# MCU3.net
KiCad netlist of a schematic drawn in Altium Designer
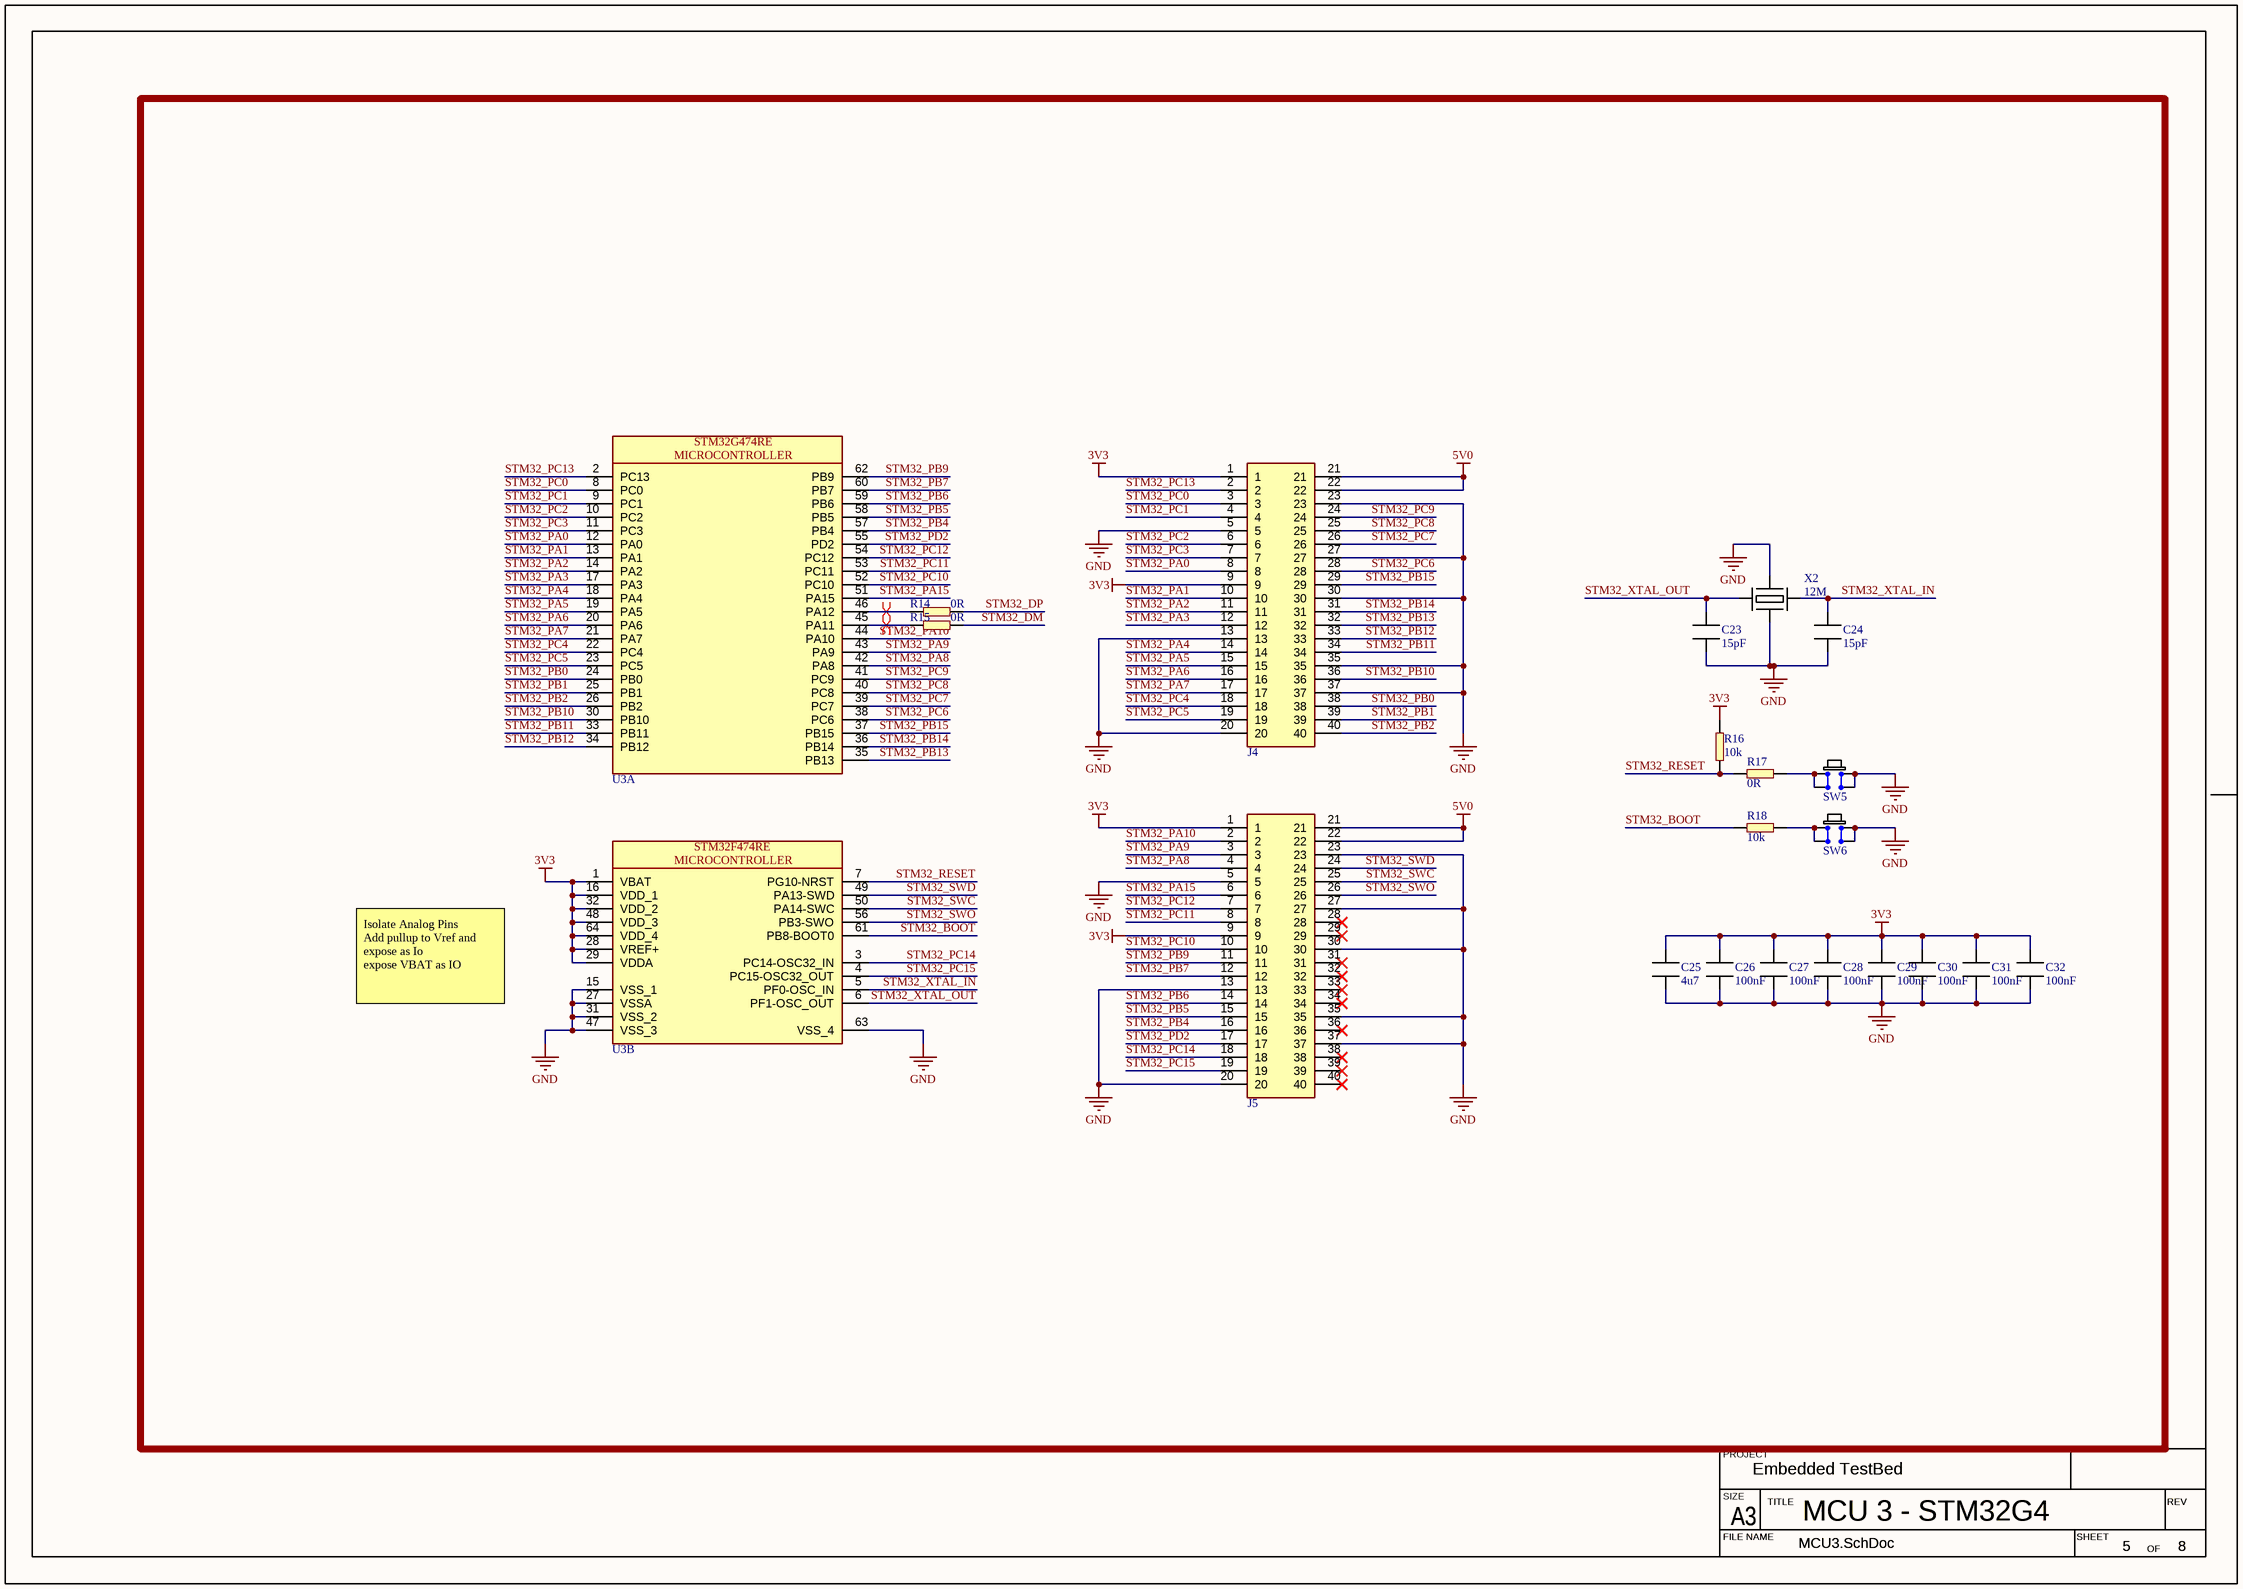
[diagram p0: MCU3.SchDoc]

(export (version "E")
  (design (tool "Eeschema 10.0.6"))
  (components
    (comp (ref "C23")
      (value "15pF")
      (footprint "CAPC2012X13L")
      (description "Chip Capacitor, 2-Leads, Body 2.00x1.25mm, IPC High Density")
      (fields (field (name "Comment") "MLCC_0805"))
      (libsource (lib "Capacitor") (part "MLCC_0805"))
    )
    (comp (ref "C24")
      (value "15pF")
      (footprint "CAPC2012X13L")
      (description "Chip Capacitor, 2-Leads, Body 2.00x1.25mm, IPC High Density")
      (fields (field (name "Comment") "MLCC_0805"))
      (libsource (lib "Capacitor") (part "MLCC_0805"))
    )
    (comp (ref "C25")
      (value "4u7")
      (footprint "CAPC2012X13L")
      (description "Chip Capacitor, 2-Leads, Body 2.00x1.25mm, IPC High Density")
      (fields (field (name "Comment") "MLCC_0805"))
      (libsource (lib "Capacitor") (part "MLCC_0805"))
    )
    (comp (ref "C26")
      (value "100nF")
      (footprint "CAPC2012X13L")
      (description "Chip Capacitor, 2-Leads, Body 2.00x1.25mm, IPC High Density")
      (fields (field (name "Comment") "MLCC_0805"))
      (libsource (lib "Capacitor") (part "MLCC_0805"))
    )
    (comp (ref "C27")
      (value "100nF")
      (footprint "CAPC2012X13L")
      (description "Chip Capacitor, 2-Leads, Body 2.00x1.25mm, IPC High Density")
      (fields (field (name "Comment") "MLCC_0805"))
      (libsource (lib "Capacitor") (part "MLCC_0805"))
    )
    (comp (ref "C28")
      (value "100nF")
      (footprint "CAPC2012X13L")
      (description "Chip Capacitor, 2-Leads, Body 2.00x1.25mm, IPC High Density")
      (fields (field (name "Comment") "MLCC_0805"))
      (libsource (lib "Capacitor") (part "MLCC_0805"))
    )
    (comp (ref "C29")
      (value "100nF")
      (footprint "CAPC2012X13L")
      (description "Chip Capacitor, 2-Leads, Body 2.00x1.25mm, IPC High Density")
      (fields (field (name "Comment") "MLCC_0805"))
      (libsource (lib "Capacitor") (part "MLCC_0805"))
    )
    (comp (ref "C30")
      (value "100nF")
      (footprint "CAPC2012X13L")
      (description "Chip Capacitor, 2-Leads, Body 2.00x1.25mm, IPC High Density")
      (fields (field (name "Comment") "MLCC_0805"))
      (libsource (lib "Capacitor") (part "MLCC_0805"))
    )
    (comp (ref "C31")
      (value "100nF")
      (footprint "CAPC2012X13L")
      (description "Chip Capacitor, 2-Leads, Body 2.00x1.25mm, IPC High Density")
      (fields (field (name "Comment") "MLCC_0805"))
      (libsource (lib "Capacitor") (part "MLCC_0805"))
    )
    (comp (ref "C32")
      (value "100nF")
      (footprint "CAPC2012X13L")
      (description "Chip Capacitor, 2-Leads, Body 2.00x1.25mm, IPC High Density")
      (fields (field (name "Comment") "MLCC_0805"))
      (libsource (lib "Capacitor") (part "MLCC_0805"))
    )
    (comp (ref "J4")
      (value "40PX2R_M_1")
      (footprint "40PX2R_Male_THT")
      (description "Berg Connector Header Through Hole  40 Position 0.100\" (2.54mm)")
      (libsource (lib "PinHeader") (part "40PX2R_M_1"))
    )
    (comp (ref "J5")
      (value "40PX2R_M_1")
      (footprint "40PX2R_Male_THT")
      (description "Berg Connector Header Through Hole  40 Position 0.100\" (2.54mm)")
      (libsource (lib "PinHeader") (part "40PX2R_M_1"))
    )
    (comp (ref "R14")
      (value "0R")
      (footprint "RES_0805")
      (description "RES_0805")
      (fields (field (name "Comment") "ERP_101-1"))
      (libsource (lib "Resistor") (part "RES_0805"))
    )
    (comp (ref "R15")
      (value "0R")
      (footprint "RES_0805")
      (description "RES_0805")
      (fields (field (name "Comment") "ERP_101-1"))
      (libsource (lib "Resistor") (part "RES_0805"))
    )
    (comp (ref "R16")
      (value "10k")
      (footprint "RES_0805")
      (description "RES_0805")
      (fields (field (name "Comment") "ERP_101-1"))
      (libsource (lib "") (part "RES_0805_1"))
    )
    (comp (ref "R17")
      (value "0R")
      (footprint "RES_0805")
      (description "RES_0805")
      (fields (field (name "Comment") "ERP_101-1"))
      (libsource (lib "Resistor") (part "RES_0805"))
    )
    (comp (ref "R18")
      (value "10k")
      (footprint "RES_0805")
      (description "RES_0805")
      (fields (field (name "Comment") "ERP_101-1"))
      (libsource (lib "Resistor") (part "RES_0805"))
    )
    (comp (ref "SW5")
      (value "Generic6X6")
      (footprint "Generic6X6")
      (description "Tactile Switch SPST-NO Top Actuated Surface Mount")
      (libsource (lib "Switch") (part "Generic6X6"))
    )
    (comp (ref "SW6")
      (value "Generic6X6")
      (footprint "Generic6X6")
      (description "Tactile Switch SPST-NO Top Actuated Surface Mount")
      (libsource (lib "Switch") (part "Generic6X6"))
    )
    (comp (ref "U3")
      (value "STM32G474RE")
      (footprint "TSQFP50P1200X1200X160-64L")
      (description "512KB 1.71V~3.6V ARM-M4 128KB 170MHz FLASH 52 LQFP-64(10x10) Microcontrollers (MCU/MPU/SOC) ROHS")
      (libsource (lib "MCU") (part "STM32G474RE"))
    )
    (comp (ref "X2")
      (value "12M")
      (footprint "ABM8")
      (description "CRYS_L3.2_W2.5")
      (fields (field (name "Comment") "ABM8"))
      (libsource (lib "Crystal") (part "ABM8"))
    )
  )
  (nets
    (net (code "1") (name "/STM32_BOOT") (class "Default")
      (node (ref "R18") (pin "2") (pinfunction "2_2") (pintype "passive"))
      (node (ref "U3") (pin "61") (pinfunction "PB8-BOOT0_61") (pintype "passive"))
    )
    (net (code "2") (name "/STM32_DM") (class "Default")
      (node (ref "R15") (pin "1") (pinfunction "1_1") (pintype "passive"))
    )
    (net (code "3") (name "/STM32_DP") (class "Default")
      (node (ref "R14") (pin "1") (pinfunction "1_1") (pintype "passive"))
    )
    (net (code "4") (name "/STM32_PA0") (class "Default")
      (node (ref "J4") (pin "8") (pinfunction "8_8") (pintype "passive"))
      (node (ref "U3") (pin "12") (pinfunction "PA0_12") (pintype "passive"))
    )
    (net (code "5") (name "/STM32_PA1") (class "Default")
      (node (ref "J4") (pin "10") (pinfunction "10_10") (pintype "passive"))
      (node (ref "U3") (pin "13") (pinfunction "PA1_13") (pintype "passive"))
    )
    (net (code "6") (name "/STM32_PA2") (class "Default")
      (node (ref "J4") (pin "11") (pinfunction "11_11") (pintype "passive"))
      (node (ref "U3") (pin "14") (pinfunction "PA2_14") (pintype "passive"))
    )
    (net (code "7") (name "/STM32_PA3") (class "Default")
      (node (ref "J4") (pin "12") (pinfunction "12_12") (pintype "passive"))
      (node (ref "U3") (pin "17") (pinfunction "PA3_17") (pintype "passive"))
    )
    (net (code "8") (name "/STM32_PA4") (class "Default")
      (node (ref "J4") (pin "14") (pinfunction "14_14") (pintype "passive"))
      (node (ref "U3") (pin "18") (pinfunction "PA4_18") (pintype "passive"))
    )
    (net (code "9") (name "/STM32_PA5") (class "Default")
      (node (ref "J4") (pin "15") (pinfunction "15_15") (pintype "passive"))
      (node (ref "U3") (pin "19") (pinfunction "PA5_19") (pintype "passive"))
    )
    (net (code "10") (name "/STM32_PA6") (class "Default")
      (node (ref "J4") (pin "16") (pinfunction "16_16") (pintype "passive"))
      (node (ref "U3") (pin "20") (pinfunction "PA6_20") (pintype "passive"))
    )
    (net (code "11") (name "/STM32_PA7") (class "Default")
      (node (ref "J4") (pin "17") (pinfunction "17_17") (pintype "passive"))
      (node (ref "U3") (pin "21") (pinfunction "PA7_21") (pintype "passive"))
    )
    (net (code "12") (name "/STM32_PA8") (class "Default")
      (node (ref "J5") (pin "4") (pinfunction "4_4") (pintype "passive"))
      (node (ref "U3") (pin "42") (pinfunction "PA8_42") (pintype "passive"))
    )
    (net (code "13") (name "/STM32_PA9") (class "Default")
      (node (ref "J5") (pin "3") (pinfunction "3_3") (pintype "passive"))
      (node (ref "U3") (pin "43") (pinfunction "PA9_43") (pintype "passive"))
    )
    (net (code "14") (name "/STM32_PA10") (class "Default")
      (node (ref "J5") (pin "2") (pinfunction "2_2") (pintype "passive"))
      (node (ref "U3") (pin "44") (pinfunction "PA10_44") (pintype "passive"))
    )
    (net (code "15") (name "/STM32_PA15") (class "Default")
      (node (ref "J5") (pin "6") (pinfunction "6_6") (pintype "passive"))
      (node (ref "U3") (pin "51") (pinfunction "PA15_51") (pintype "passive"))
    )
    (net (code "16") (name "/STM32_PB0") (class "Default")
      (node (ref "J4") (pin "38") (pinfunction "38_38") (pintype "passive"))
      (node (ref "U3") (pin "24") (pinfunction "PB0_24") (pintype "passive"))
    )
    (net (code "17") (name "/STM32_PB1") (class "Default")
      (node (ref "J4") (pin "39") (pinfunction "39_39") (pintype "passive"))
      (node (ref "U3") (pin "25") (pinfunction "PB1_25") (pintype "passive"))
    )
    (net (code "18") (name "/STM32_PB2") (class "Default")
      (node (ref "J4") (pin "40") (pinfunction "40_40") (pintype "passive"))
      (node (ref "U3") (pin "26") (pinfunction "PB2_26") (pintype "passive"))
    )
    (net (code "19") (name "/STM32_PB4") (class "Default")
      (node (ref "J5") (pin "16") (pinfunction "16_16") (pintype "passive"))
      (node (ref "U3") (pin "57") (pinfunction "PB4_57") (pintype "passive"))
    )
    (net (code "20") (name "/STM32_PB5") (class "Default")
      (node (ref "J5") (pin "15") (pinfunction "15_15") (pintype "passive"))
      (node (ref "U3") (pin "58") (pinfunction "PB5_58") (pintype "passive"))
    )
    (net (code "21") (name "/STM32_PB6") (class "Default")
      (node (ref "J5") (pin "14") (pinfunction "14_14") (pintype "passive"))
      (node (ref "U3") (pin "59") (pinfunction "PB6_59") (pintype "passive"))
    )
    (net (code "22") (name "/STM32_PB7") (class "Default")
      (node (ref "J5") (pin "12") (pinfunction "12_12") (pintype "passive"))
      (node (ref "U3") (pin "60") (pinfunction "PB7_60") (pintype "passive"))
    )
    (net (code "23") (name "/STM32_PB9") (class "Default")
      (node (ref "J5") (pin "11") (pinfunction "11_11") (pintype "passive"))
      (node (ref "U3") (pin "62") (pinfunction "PB9_62") (pintype "passive"))
    )
    (net (code "24") (name "/STM32_PB10") (class "Default")
      (node (ref "J4") (pin "36") (pinfunction "36_36") (pintype "passive"))
      (node (ref "U3") (pin "30") (pinfunction "PB10_30") (pintype "passive"))
    )
    (net (code "25") (name "/STM32_PB11") (class "Default")
      (node (ref "J4") (pin "34") (pinfunction "34_34") (pintype "passive"))
      (node (ref "U3") (pin "33") (pinfunction "PB11_33") (pintype "passive"))
    )
    (net (code "26") (name "/STM32_PB12") (class "Default")
      (node (ref "J4") (pin "33") (pinfunction "33_33") (pintype "passive"))
      (node (ref "U3") (pin "34") (pinfunction "PB12_34") (pintype "passive"))
    )
    (net (code "27") (name "/STM32_PB13") (class "Default")
      (node (ref "J4") (pin "32") (pinfunction "32_32") (pintype "passive"))
      (node (ref "U3") (pin "35") (pinfunction "PB13_35") (pintype "passive"))
    )
    (net (code "28") (name "/STM32_PB14") (class "Default")
      (node (ref "J4") (pin "31") (pinfunction "31_31") (pintype "passive"))
      (node (ref "U3") (pin "36") (pinfunction "PB14_36") (pintype "passive"))
    )
    (net (code "29") (name "/STM32_PB15") (class "Default")
      (node (ref "J4") (pin "29") (pinfunction "29_29") (pintype "passive"))
      (node (ref "U3") (pin "37") (pinfunction "PB15_37") (pintype "passive"))
    )
    (net (code "30") (name "/STM32_PC0") (class "Default")
      (node (ref "J4") (pin "3") (pinfunction "3_3") (pintype "passive"))
      (node (ref "U3") (pin "8") (pinfunction "PC0_8") (pintype "passive"))
    )
    (net (code "31") (name "/STM32_PC1") (class "Default")
      (node (ref "J4") (pin "4") (pinfunction "4_4") (pintype "passive"))
      (node (ref "U3") (pin "9") (pinfunction "PC1_9") (pintype "passive"))
    )
    (net (code "32") (name "/STM32_PC2") (class "Default")
      (node (ref "J4") (pin "6") (pinfunction "6_6") (pintype "passive"))
      (node (ref "U3") (pin "10") (pinfunction "PC2_10") (pintype "passive"))
    )
    (net (code "33") (name "/STM32_PC3") (class "Default")
      (node (ref "J4") (pin "7") (pinfunction "7_7") (pintype "passive"))
      (node (ref "U3") (pin "11") (pinfunction "PC3_11") (pintype "passive"))
    )
    (net (code "34") (name "/STM32_PC4") (class "Default")
      (node (ref "J4") (pin "18") (pinfunction "18_18") (pintype "passive"))
      (node (ref "U3") (pin "22") (pinfunction "PC4_22") (pintype "passive"))
    )
    (net (code "35") (name "/STM32_PC5") (class "Default")
      (node (ref "J4") (pin "19") (pinfunction "19_19") (pintype "passive"))
      (node (ref "U3") (pin "23") (pinfunction "PC5_23") (pintype "passive"))
    )
    (net (code "36") (name "/STM32_PC6") (class "Default")
      (node (ref "J4") (pin "28") (pinfunction "28_28") (pintype "passive"))
      (node (ref "U3") (pin "38") (pinfunction "PC6_38") (pintype "passive"))
    )
    (net (code "37") (name "/STM32_PC7") (class "Default")
      (node (ref "J4") (pin "26") (pinfunction "26_26") (pintype "passive"))
      (node (ref "U3") (pin "39") (pinfunction "PC7_39") (pintype "passive"))
    )
    (net (code "38") (name "/STM32_PC8") (class "Default")
      (node (ref "J4") (pin "25") (pinfunction "25_25") (pintype "passive"))
      (node (ref "U3") (pin "40") (pinfunction "PC8_40") (pintype "passive"))
    )
    (net (code "39") (name "/STM32_PC9") (class "Default")
      (node (ref "J4") (pin "24") (pinfunction "24_24") (pintype "passive"))
      (node (ref "U3") (pin "41") (pinfunction "PC9_41") (pintype "passive"))
    )
    (net (code "40") (name "/STM32_PC10") (class "Default")
      (node (ref "J5") (pin "10") (pinfunction "10_10") (pintype "passive"))
      (node (ref "U3") (pin "52") (pinfunction "PC10_52") (pintype "passive"))
    )
    (net (code "41") (name "/STM32_PC11") (class "Default")
      (node (ref "J5") (pin "8") (pinfunction "8_8") (pintype "passive"))
      (node (ref "U3") (pin "53") (pinfunction "PC11_53") (pintype "passive"))
    )
    (net (code "42") (name "/STM32_PC12") (class "Default")
      (node (ref "J5") (pin "7") (pinfunction "7_7") (pintype "passive"))
      (node (ref "U3") (pin "54") (pinfunction "PC12_54") (pintype "passive"))
    )
    (net (code "43") (name "/STM32_PC13") (class "Default")
      (node (ref "J4") (pin "2") (pinfunction "2_2") (pintype "passive"))
      (node (ref "U3") (pin "2") (pinfunction "PC13_2") (pintype "passive"))
    )
    (net (code "44") (name "/STM32_PC14") (class "Default")
      (node (ref "J5") (pin "18") (pinfunction "18_18") (pintype "passive"))
      (node (ref "U3") (pin "3") (pinfunction "PC14-OSC32_IN_3") (pintype "passive"))
    )
    (net (code "45") (name "/STM32_PC15") (class "Default")
      (node (ref "J5") (pin "19") (pinfunction "19_19") (pintype "passive"))
      (node (ref "U3") (pin "4") (pinfunction "PC15-OSC32_OUT_4") (pintype "passive"))
    )
    (net (code "46") (name "/STM32_PD2") (class "Default")
      (node (ref "J5") (pin "17") (pinfunction "17_17") (pintype "passive"))
      (node (ref "U3") (pin "55") (pinfunction "PD2_55") (pintype "passive"))
    )
    (net (code "47") (name "/STM32_RESET") (class "Default")
      (node (ref "R16") (pin "2") (pinfunction "2_2") (pintype "passive"))
      (node (ref "R17") (pin "2") (pinfunction "2_2") (pintype "passive"))
      (node (ref "U3") (pin "7") (pinfunction "PG10-NRST_7") (pintype "passive"))
    )
    (net (code "48") (name "/STM32_SWC") (class "Default")
      (node (ref "J5") (pin "25") (pinfunction "25_25") (pintype "passive"))
      (node (ref "U3") (pin "50") (pinfunction "PA14-SWC_50") (pintype "passive"))
    )
    (net (code "49") (name "/STM32_SWD") (class "Default")
      (node (ref "J5") (pin "24") (pinfunction "24_24") (pintype "passive"))
      (node (ref "U3") (pin "49") (pinfunction "PA13-SWD_49") (pintype "passive"))
    )
    (net (code "50") (name "/STM32_SWO") (class "Default")
      (node (ref "J5") (pin "26") (pinfunction "26_26") (pintype "passive"))
      (node (ref "U3") (pin "56") (pinfunction "PB3-SWO_56") (pintype "passive"))
    )
    (net (code "51") (name "/STM32_XTAL_IN") (class "Default")
      (node (ref "C24") (pin "1") (pinfunction "1_1") (pintype "passive"))
      (node (ref "U3") (pin "5") (pinfunction "PF0-OSC_IN_5") (pintype "passive"))
      (node (ref "X2") (pin "3") (pinfunction "3_3") (pintype "passive"))
    )
    (net (code "52") (name "/STM32_XTAL_OUT") (class "Default")
      (node (ref "C23") (pin "1") (pinfunction "1_1") (pintype "passive"))
      (node (ref "U3") (pin "6") (pinfunction "PF1-OSC_OUT_6") (pintype "passive"))
      (node (ref "X2") (pin "1") (pinfunction "1_1") (pintype "passive"))
    )
    (net (code "53") (name "3V3") (class "Default")
      (node (ref "C25") (pin "1") (pinfunction "1_1") (pintype "passive"))
      (node (ref "C26") (pin "1") (pinfunction "1_1") (pintype "passive"))
      (node (ref "C27") (pin "1") (pinfunction "1_1") (pintype "passive"))
      (node (ref "C28") (pin "1") (pinfunction "1_1") (pintype "passive"))
      (node (ref "C29") (pin "1") (pinfunction "1_1") (pintype "passive"))
      (node (ref "C30") (pin "1") (pinfunction "1_1") (pintype "passive"))
      (node (ref "C31") (pin "1") (pinfunction "1_1") (pintype "passive"))
      (node (ref "C32") (pin "1") (pinfunction "1_1") (pintype "passive"))
      (node (ref "J4") (pin "1") (pinfunction "1_1") (pintype "passive"))
      (node (ref "J4") (pin "9") (pinfunction "9_9") (pintype "passive"))
      (node (ref "J5") (pin "1") (pinfunction "1_1") (pintype "passive"))
      (node (ref "J5") (pin "9") (pinfunction "9_9") (pintype "passive"))
      (node (ref "R16") (pin "1") (pinfunction "1_1") (pintype "passive"))
      (node (ref "U3") (pin "1") (pinfunction "VBAT_1") (pintype "passive"))
      (node (ref "U3") (pin "16") (pinfunction "VDD_1_16") (pintype "passive"))
      (node (ref "U3") (pin "28") (pinfunction "VREF+_28") (pintype "passive"))
      (node (ref "U3") (pin "29") (pinfunction "VDDA_29") (pintype "passive"))
      (node (ref "U3") (pin "32") (pinfunction "VDD_2_32") (pintype "passive"))
      (node (ref "U3") (pin "48") (pinfunction "VDD_3_48") (pintype "passive"))
      (node (ref "U3") (pin "64") (pinfunction "VDD_4_64") (pintype "passive"))
    )
    (net (code "54") (name "5V0") (class "Default")
      (node (ref "J4") (pin "21") (pinfunction "21_21") (pintype "passive"))
      (node (ref "J4") (pin "22") (pinfunction "22_22") (pintype "passive"))
      (node (ref "J5") (pin "21") (pinfunction "21_21") (pintype "passive"))
      (node (ref "J5") (pin "22") (pinfunction "22_22") (pintype "passive"))
    )
    (net (code "55") (name "GND") (class "Default")
      (node (ref "C23") (pin "2") (pinfunction "2_2") (pintype "passive"))
      (node (ref "C24") (pin "2") (pinfunction "2_2") (pintype "passive"))
      (node (ref "C25") (pin "2") (pinfunction "2_2") (pintype "passive"))
      (node (ref "C26") (pin "2") (pinfunction "2_2") (pintype "passive"))
      (node (ref "C27") (pin "2") (pinfunction "2_2") (pintype "passive"))
      (node (ref "C28") (pin "2") (pinfunction "2_2") (pintype "passive"))
      (node (ref "C29") (pin "2") (pinfunction "2_2") (pintype "passive"))
      (node (ref "C30") (pin "2") (pinfunction "2_2") (pintype "passive"))
      (node (ref "C31") (pin "2") (pinfunction "2_2") (pintype "passive"))
      (node (ref "C32") (pin "2") (pinfunction "2_2") (pintype "passive"))
      (node (ref "J4") (pin "13") (pinfunction "13_13") (pintype "passive"))
      (node (ref "J4") (pin "20") (pinfunction "20_20") (pintype "passive"))
      (node (ref "J4") (pin "23") (pinfunction "23_23") (pintype "passive"))
      (node (ref "J4") (pin "27") (pinfunction "27_27") (pintype "passive"))
      (node (ref "J4") (pin "30") (pinfunction "30_30") (pintype "passive"))
      (node (ref "J4") (pin "35") (pinfunction "35_35") (pintype "passive"))
      (node (ref "J4") (pin "37") (pinfunction "37_37") (pintype "passive"))
      (node (ref "J4") (pin "5") (pinfunction "5_5") (pintype "passive"))
      (node (ref "J5") (pin "13") (pinfunction "13_13") (pintype "passive"))
      (node (ref "J5") (pin "20") (pinfunction "20_20") (pintype "passive"))
      (node (ref "J5") (pin "23") (pinfunction "23_23") (pintype "passive"))
      (node (ref "J5") (pin "27") (pinfunction "27_27") (pintype "passive"))
      (node (ref "J5") (pin "30") (pinfunction "30_30") (pintype "passive"))
      (node (ref "J5") (pin "35") (pinfunction "35_35") (pintype "passive"))
      (node (ref "J5") (pin "37") (pinfunction "37_37") (pintype "passive"))
      (node (ref "J5") (pin "5") (pinfunction "5_5") (pintype "passive"))
      (node (ref "SW5") (pin "3") (pinfunction "COM_3") (pintype "passive"))
      (node (ref "SW5") (pin "4") (pinfunction "COM_4") (pintype "passive"))
      (node (ref "SW6") (pin "3") (pinfunction "COM_3") (pintype "passive"))
      (node (ref "SW6") (pin "4") (pinfunction "COM_4") (pintype "passive"))
      (node (ref "U3") (pin "15") (pinfunction "VSS_1_15") (pintype "passive"))
      (node (ref "U3") (pin "27") (pinfunction "VSSA_27") (pintype "passive"))
      (node (ref "U3") (pin "31") (pinfunction "VSS_2_31") (pintype "passive"))
      (node (ref "U3") (pin "47") (pinfunction "VSS_3_47") (pintype "passive"))
      (node (ref "U3") (pin "63") (pinfunction "VSS_4_63") (pintype "passive"))
      (node (ref "X2") (pin "2") (pinfunction "2_2") (pintype "passive"))
      (node (ref "X2") (pin "4") (pinfunction "4_4") (pintype "passive"))
    )
    (net (code "56") (name "Net-(R17-Pad1)") (class "Default")
      (node (ref "R17") (pin "1") (pinfunction "1_1") (pintype "passive"))
      (node (ref "SW5") (pin "1") (pinfunction "NO_1") (pintype "passive"))
      (node (ref "SW5") (pin "2") (pinfunction "NO_2") (pintype "passive"))
    )
    (net (code "57") (name "Net-(R18-Pad1)") (class "Default")
      (node (ref "R18") (pin "1") (pinfunction "1_1") (pintype "passive"))
      (node (ref "SW6") (pin "1") (pinfunction "NO_1") (pintype "passive"))
      (node (ref "SW6") (pin "2") (pinfunction "NO_2") (pintype "passive"))
    )
    (net (code "58") (name "Net-(U3A-PA11)") (class "Default")
      (node (ref "R15") (pin "2") (pinfunction "2_2") (pintype "passive"))
      (node (ref "U3") (pin "45") (pinfunction "PA11_45") (pintype "passive"))
    )
    (net (code "59") (name "Net-(U3A-PA12)") (class "Default")
      (node (ref "R14") (pin "2") (pinfunction "2_2") (pintype "passive"))
      (node (ref "U3") (pin "46") (pinfunction "PA12_46") (pintype "passive"))
    )
    (net (code "60") (name "unconnected-(J5-Pad28)") (class "Default")
      (node (ref "J5") (pin "28") (pinfunction "28_28") (pintype "passive+no_connect"))
    )
    (net (code "61") (name "unconnected-(J5-Pad29)") (class "Default")
      (node (ref "J5") (pin "29") (pinfunction "29_29") (pintype "passive+no_connect"))
    )
    (net (code "62") (name "unconnected-(J5-Pad31)") (class "Default")
      (node (ref "J5") (pin "31") (pinfunction "31_31") (pintype "passive+no_connect"))
    )
    (net (code "63") (name "unconnected-(J5-Pad32)") (class "Default")
      (node (ref "J5") (pin "32") (pinfunction "32_32") (pintype "passive+no_connect"))
    )
    (net (code "64") (name "unconnected-(J5-Pad33)") (class "Default")
      (node (ref "J5") (pin "33") (pinfunction "33_33") (pintype "passive+no_connect"))
    )
    (net (code "65") (name "unconnected-(J5-Pad34)") (class "Default")
      (node (ref "J5") (pin "34") (pinfunction "34_34") (pintype "passive+no_connect"))
    )
    (net (code "66") (name "unconnected-(J5-Pad36)") (class "Default")
      (node (ref "J5") (pin "36") (pinfunction "36_36") (pintype "passive+no_connect"))
    )
    (net (code "67") (name "unconnected-(J5-Pad38)") (class "Default")
      (node (ref "J5") (pin "38") (pinfunction "38_38") (pintype "passive+no_connect"))
    )
    (net (code "68") (name "unconnected-(J5-Pad39)") (class "Default")
      (node (ref "J5") (pin "39") (pinfunction "39_39") (pintype "passive+no_connect"))
    )
    (net (code "69") (name "unconnected-(J5-Pad40)") (class "Default")
      (node (ref "J5") (pin "40") (pinfunction "40_40") (pintype "passive+no_connect"))
    )
  )
)
